# Sheet_2.net
KiCad netlist of a schematic drawn in EasyEDA
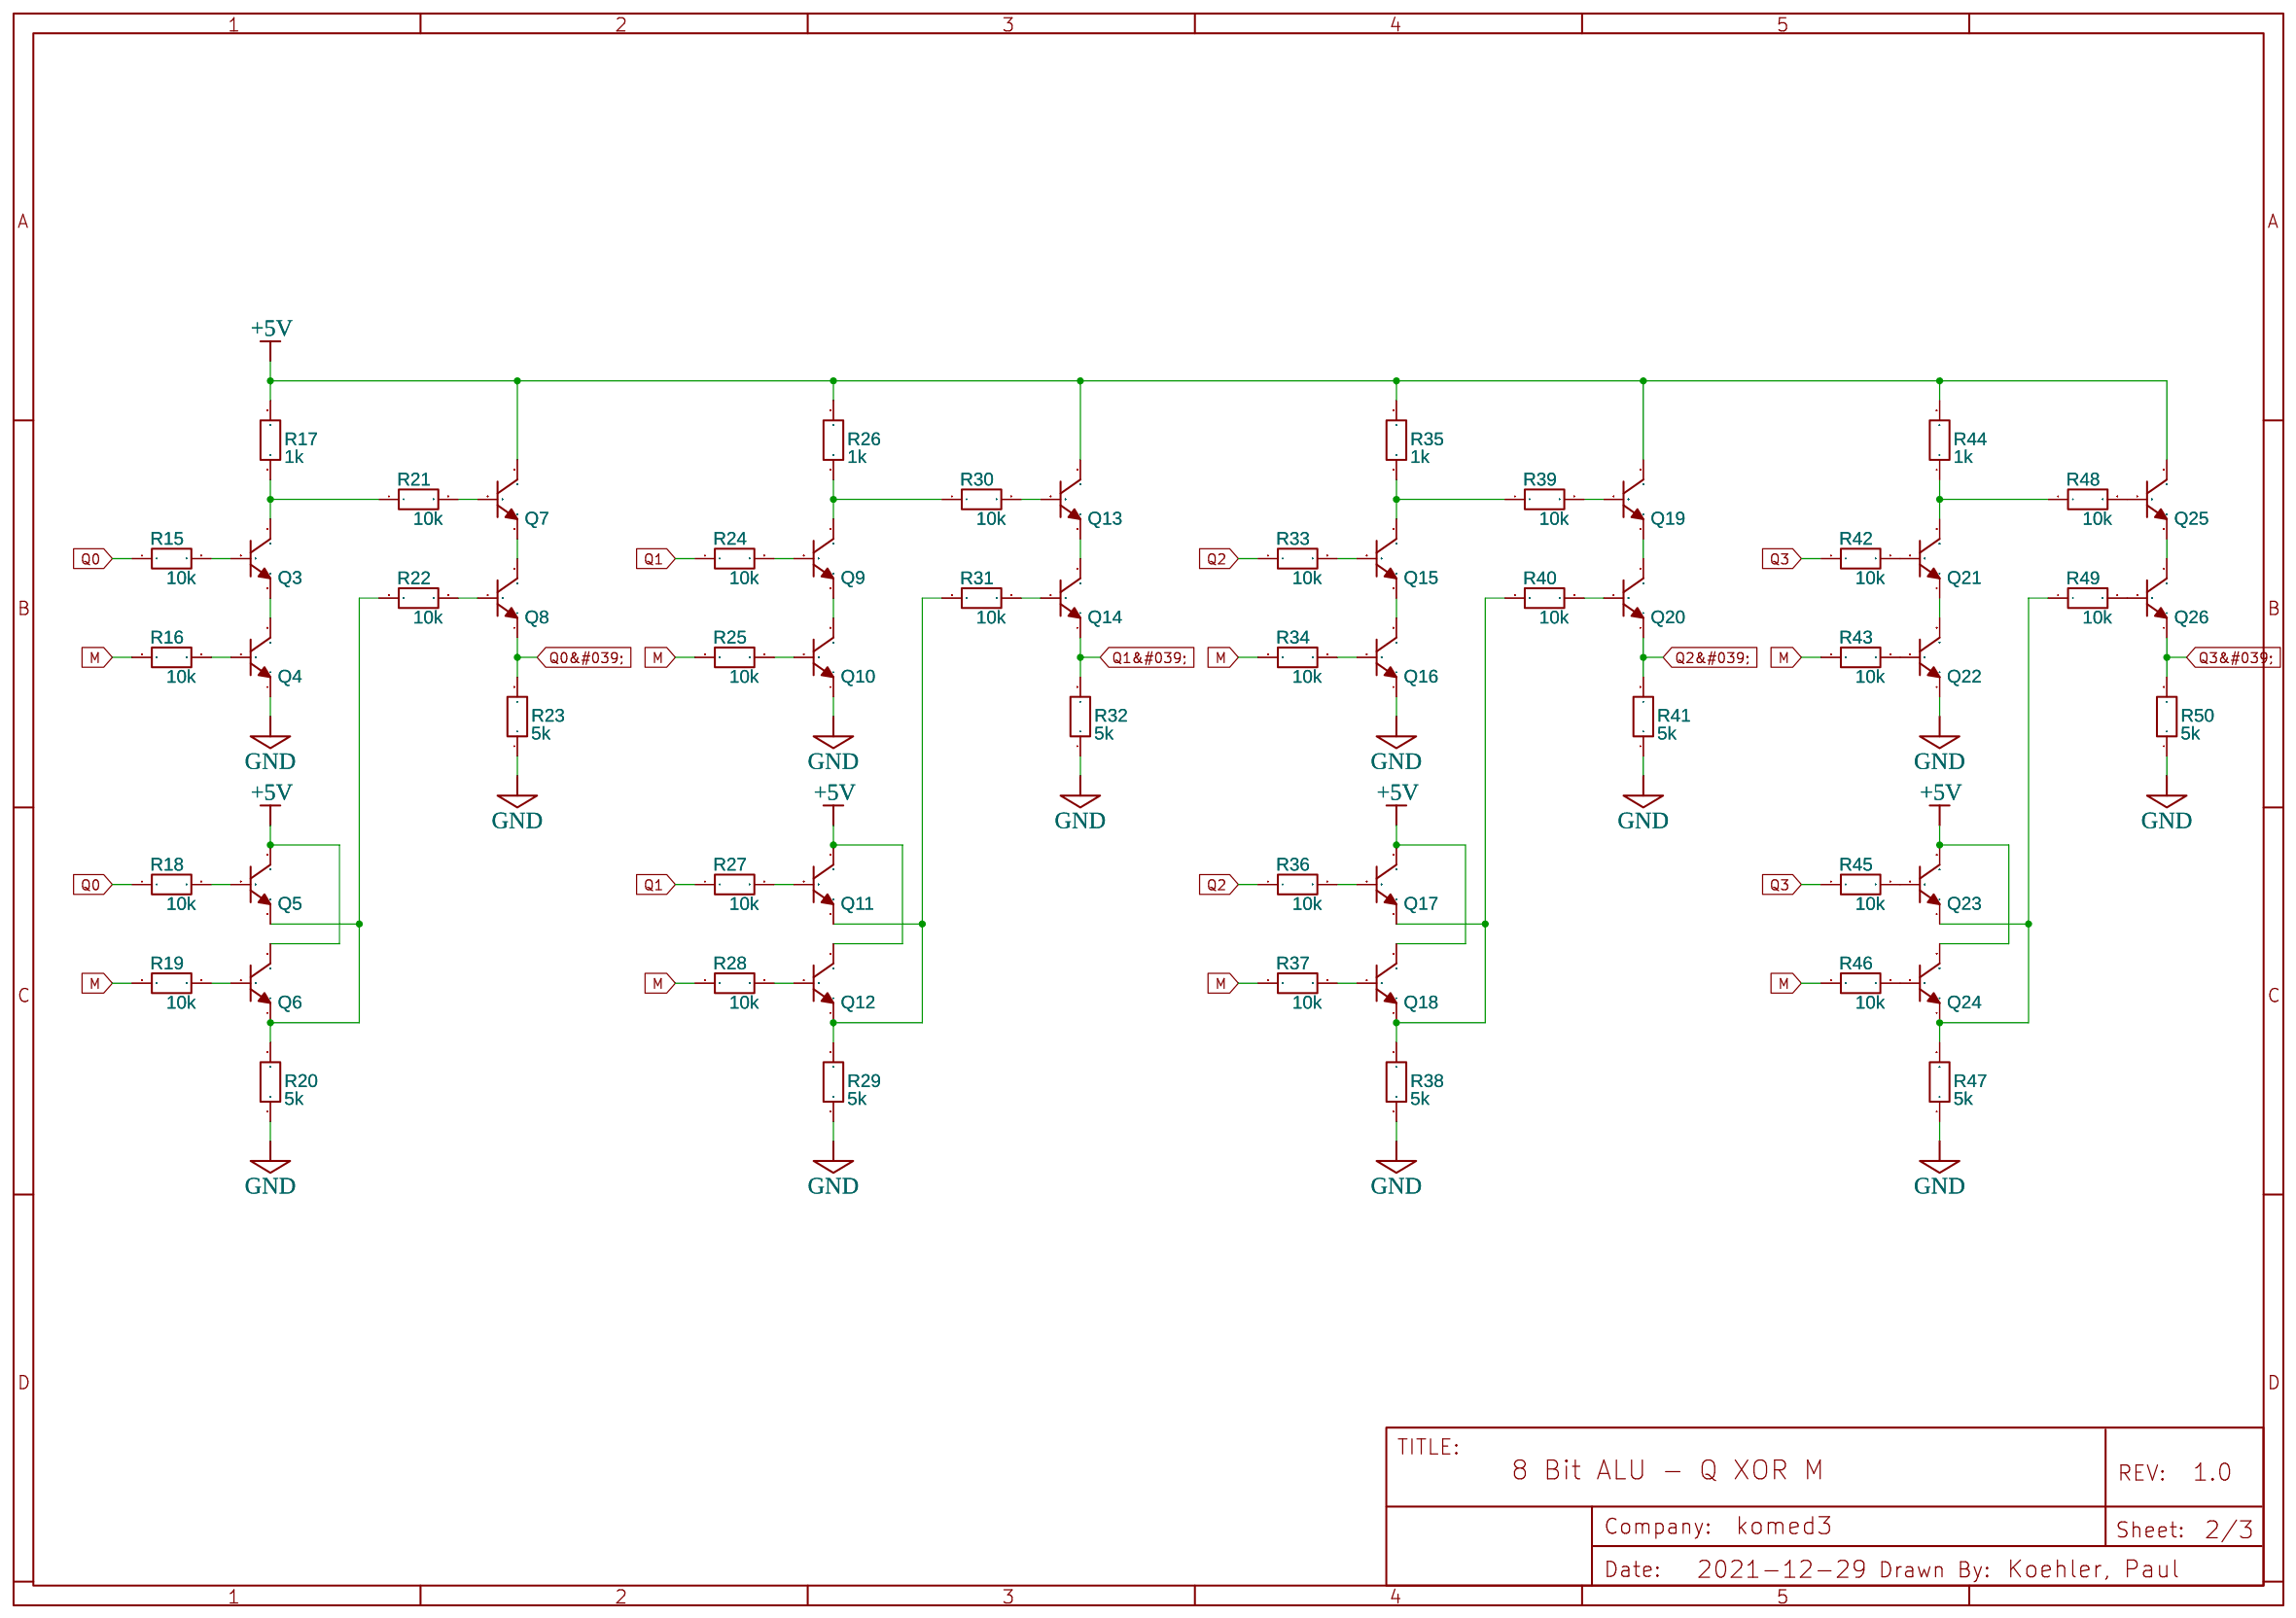
[diagram p0: schematic sheet]

(export (version "E")
  (design (tool "Eeschema 10.0.6"))
  (components
    (comp (ref "Q3")
      (value "2N3904(TO-92)")
      (fields (field (name "BOM_Manufacturer Part") "2N3904") (field (name "BOM_Supplier Part") "C118538"))
      (libsource (lib "") (part "2N3904(TO-92)"))
    )
    (comp (ref "Q4")
      (value "2N3904(TO-92)")
      (fields (field (name "BOM_Manufacturer Part") "2N3904") (field (name "BOM_Supplier Part") "C118538"))
      (libsource (lib "") (part "2N3904(TO-92)"))
    )
    (comp (ref "Q5")
      (value "2N3904(TO-92)")
      (fields (field (name "BOM_Manufacturer Part") "2N3904") (field (name "BOM_Supplier Part") "C118538"))
      (libsource (lib "") (part "2N3904(TO-92)"))
    )
    (comp (ref "Q6")
      (value "2N3904(TO-92)")
      (fields (field (name "BOM_Manufacturer Part") "2N3904") (field (name "BOM_Supplier Part") "C118538"))
      (libsource (lib "") (part "2N3904(TO-92)"))
    )
    (comp (ref "Q7")
      (value "2N3904(TO-92)")
      (fields (field (name "BOM_Manufacturer Part") "2N3904") (field (name "BOM_Supplier Part") "C118538"))
      (libsource (lib "") (part "2N3904(TO-92)"))
    )
    (comp (ref "Q8")
      (value "2N3904(TO-92)")
      (fields (field (name "BOM_Manufacturer Part") "2N3904") (field (name "BOM_Supplier Part") "C118538"))
      (libsource (lib "") (part "2N3904(TO-92)"))
    )
    (comp (ref "Q9")
      (value "2N3904(TO-92)")
      (fields (field (name "BOM_Manufacturer Part") "2N3904") (field (name "BOM_Supplier Part") "C118538"))
      (libsource (lib "") (part "2N3904(TO-92)"))
    )
    (comp (ref "Q10")
      (value "2N3904(TO-92)")
      (fields (field (name "BOM_Manufacturer Part") "2N3904") (field (name "BOM_Supplier Part") "C118538"))
      (libsource (lib "") (part "2N3904(TO-92)"))
    )
    (comp (ref "Q11")
      (value "2N3904(TO-92)")
      (fields (field (name "BOM_Manufacturer Part") "2N3904") (field (name "BOM_Supplier Part") "C118538"))
      (libsource (lib "") (part "2N3904(TO-92)"))
    )
    (comp (ref "Q12")
      (value "2N3904(TO-92)")
      (fields (field (name "BOM_Manufacturer Part") "2N3904") (field (name "BOM_Supplier Part") "C118538"))
      (libsource (lib "") (part "2N3904(TO-92)"))
    )
    (comp (ref "Q13")
      (value "2N3904(TO-92)")
      (fields (field (name "BOM_Manufacturer Part") "2N3904") (field (name "BOM_Supplier Part") "C118538"))
      (libsource (lib "") (part "2N3904(TO-92)"))
    )
    (comp (ref "Q14")
      (value "2N3904(TO-92)")
      (fields (field (name "BOM_Manufacturer Part") "2N3904") (field (name "BOM_Supplier Part") "C118538"))
      (libsource (lib "") (part "2N3904(TO-92)"))
    )
    (comp (ref "Q15")
      (value "2N3904(TO-92)")
      (fields (field (name "BOM_Manufacturer Part") "2N3904") (field (name "BOM_Supplier Part") "C118538"))
      (libsource (lib "") (part "2N3904(TO-92)"))
    )
    (comp (ref "Q16")
      (value "2N3904(TO-92)")
      (fields (field (name "BOM_Manufacturer Part") "2N3904") (field (name "BOM_Supplier Part") "C118538"))
      (libsource (lib "") (part "2N3904(TO-92)"))
    )
    (comp (ref "Q17")
      (value "2N3904(TO-92)")
      (fields (field (name "BOM_Manufacturer Part") "2N3904") (field (name "BOM_Supplier Part") "C118538"))
      (libsource (lib "") (part "2N3904(TO-92)"))
    )
    (comp (ref "Q18")
      (value "2N3904(TO-92)")
      (fields (field (name "BOM_Manufacturer Part") "2N3904") (field (name "BOM_Supplier Part") "C118538"))
      (libsource (lib "") (part "2N3904(TO-92)"))
    )
    (comp (ref "Q19")
      (value "2N3904(TO-92)")
      (fields (field (name "BOM_Manufacturer Part") "2N3904") (field (name "BOM_Supplier Part") "C118538"))
      (libsource (lib "") (part "2N3904(TO-92)"))
    )
    (comp (ref "Q20")
      (value "2N3904(TO-92)")
      (fields (field (name "BOM_Manufacturer Part") "2N3904") (field (name "BOM_Supplier Part") "C118538"))
      (libsource (lib "") (part "2N3904(TO-92)"))
    )
    (comp (ref "Q21")
      (value "2N3904(TO-92)")
      (fields (field (name "BOM_Manufacturer Part") "2N3904") (field (name "BOM_Supplier Part") "C118538"))
      (libsource (lib "") (part "2N3904(TO-92)"))
    )
    (comp (ref "Q22")
      (value "2N3904(TO-92)")
      (fields (field (name "BOM_Manufacturer Part") "2N3904") (field (name "BOM_Supplier Part") "C118538"))
      (libsource (lib "") (part "2N3904(TO-92)"))
    )
    (comp (ref "Q23")
      (value "2N3904(TO-92)")
      (fields (field (name "BOM_Manufacturer Part") "2N3904") (field (name "BOM_Supplier Part") "C118538"))
      (libsource (lib "") (part "2N3904(TO-92)"))
    )
    (comp (ref "Q24")
      (value "2N3904(TO-92)")
      (fields (field (name "BOM_Manufacturer Part") "2N3904") (field (name "BOM_Supplier Part") "C118538"))
      (libsource (lib "") (part "2N3904(TO-92)"))
    )
    (comp (ref "Q25")
      (value "2N3904(TO-92)")
      (fields (field (name "BOM_Manufacturer Part") "2N3904") (field (name "BOM_Supplier Part") "C118538"))
      (libsource (lib "") (part "2N3904(TO-92)"))
    )
    (comp (ref "Q26")
      (value "2N3904(TO-92)")
      (fields (field (name "BOM_Manufacturer Part") "2N3904") (field (name "BOM_Supplier Part") "C118538"))
      (libsource (lib "") (part "2N3904(TO-92)"))
    )
    (comp (ref "R15") (value "10k") (libsource (lib "") (part "R_AXIAL-0.3_EU")))
    (comp (ref "R16") (value "10k") (libsource (lib "") (part "R_AXIAL-0.3_EU")))
    (comp (ref "R17") (value "1k") (libsource (lib "") (part "R_AXIAL-0.3_EU_1")))
    (comp (ref "R18") (value "10k") (libsource (lib "") (part "R_AXIAL-0.3_EU")))
    (comp (ref "R19") (value "10k") (libsource (lib "") (part "R_AXIAL-0.3_EU")))
    (comp (ref "R20") (value "5k") (libsource (lib "") (part "R_AXIAL-0.3_EU_1")))
    (comp (ref "R21") (value "10k") (libsource (lib "") (part "R_AXIAL-0.3_EU")))
    (comp (ref "R22") (value "10k") (libsource (lib "") (part "R_AXIAL-0.3_EU")))
    (comp (ref "R23") (value "5k") (libsource (lib "") (part "R_AXIAL-0.3_EU_1")))
    (comp (ref "R24") (value "10k") (libsource (lib "") (part "R_AXIAL-0.3_EU")))
    (comp (ref "R25") (value "10k") (libsource (lib "") (part "R_AXIAL-0.3_EU")))
    (comp (ref "R26") (value "1k") (libsource (lib "") (part "R_AXIAL-0.3_EU_1")))
    (comp (ref "R27") (value "10k") (libsource (lib "") (part "R_AXIAL-0.3_EU")))
    (comp (ref "R28") (value "10k") (libsource (lib "") (part "R_AXIAL-0.3_EU")))
    (comp (ref "R29") (value "5k") (libsource (lib "") (part "R_AXIAL-0.3_EU_1")))
    (comp (ref "R30") (value "10k") (libsource (lib "") (part "R_AXIAL-0.3_EU")))
    (comp (ref "R31") (value "10k") (libsource (lib "") (part "R_AXIAL-0.3_EU")))
    (comp (ref "R32") (value "5k") (libsource (lib "") (part "R_AXIAL-0.3_EU_1")))
    (comp (ref "R33") (value "10k") (libsource (lib "") (part "R_AXIAL-0.3_EU")))
    (comp (ref "R34") (value "10k") (libsource (lib "") (part "R_AXIAL-0.3_EU")))
    (comp (ref "R35") (value "1k") (libsource (lib "") (part "R_AXIAL-0.3_EU_1")))
    (comp (ref "R36") (value "10k") (libsource (lib "") (part "R_AXIAL-0.3_EU")))
    (comp (ref "R37") (value "10k") (libsource (lib "") (part "R_AXIAL-0.3_EU")))
    (comp (ref "R38") (value "5k") (libsource (lib "") (part "R_AXIAL-0.3_EU_1")))
    (comp (ref "R39") (value "10k") (libsource (lib "") (part "R_AXIAL-0.3_EU")))
    (comp (ref "R40") (value "10k") (libsource (lib "") (part "R_AXIAL-0.3_EU")))
    (comp (ref "R41") (value "5k") (libsource (lib "") (part "R_AXIAL-0.3_EU_1")))
    (comp (ref "R42") (value "10k") (libsource (lib "") (part "R_AXIAL-0.3_EU")))
    (comp (ref "R43") (value "10k") (libsource (lib "") (part "R_AXIAL-0.3_EU")))
    (comp (ref "R44") (value "1k") (libsource (lib "") (part "R_AXIAL-0.3_EU_1")))
    (comp (ref "R45") (value "10k") (libsource (lib "") (part "R_AXIAL-0.3_EU")))
    (comp (ref "R46") (value "10k") (libsource (lib "") (part "R_AXIAL-0.3_EU")))
    (comp (ref "R47") (value "5k") (libsource (lib "") (part "R_AXIAL-0.3_EU_1")))
    (comp (ref "R48") (value "10k") (libsource (lib "") (part "R_AXIAL-0.3_EU")))
    (comp (ref "R49") (value "10k") (libsource (lib "") (part "R_AXIAL-0.3_EU")))
    (comp (ref "R50") (value "5k") (libsource (lib "") (part "R_AXIAL-0.3_EU_1")))
  )
  (nets
    (net (code "1") (name "+5V") (class "Default")
      (node (ref "Q11") (pin "3") (pinfunction "C_3") (pintype "unspecified"))
      (node (ref "Q12") (pin "3") (pinfunction "C_3") (pintype "unspecified"))
      (node (ref "Q13") (pin "3") (pinfunction "C_3") (pintype "unspecified"))
      (node (ref "Q17") (pin "3") (pinfunction "C_3") (pintype "unspecified"))
      (node (ref "Q18") (pin "3") (pinfunction "C_3") (pintype "unspecified"))
      (node (ref "Q19") (pin "3") (pinfunction "C_3") (pintype "unspecified"))
      (node (ref "Q23") (pin "3") (pinfunction "C_3") (pintype "unspecified"))
      (node (ref "Q24") (pin "3") (pinfunction "C_3") (pintype "unspecified"))
      (node (ref "Q25") (pin "3") (pinfunction "C_3") (pintype "unspecified"))
      (node (ref "Q5") (pin "3") (pinfunction "C_3") (pintype "unspecified"))
      (node (ref "Q6") (pin "3") (pinfunction "C_3") (pintype "unspecified"))
      (node (ref "Q7") (pin "3") (pinfunction "C_3") (pintype "unspecified"))
      (node (ref "R17") (pin "2") (pinfunction "2_2") (pintype "unspecified"))
      (node (ref "R26") (pin "2") (pinfunction "2_2") (pintype "unspecified"))
      (node (ref "R35") (pin "2") (pinfunction "2_2") (pintype "unspecified"))
      (node (ref "R44") (pin "2") (pinfunction "2_2") (pintype "unspecified"))
    )
    (net (code "2") (name "GND") (class "Default")
      (node (ref "Q10") (pin "1") (pinfunction "E_1") (pintype "unspecified"))
      (node (ref "Q16") (pin "1") (pinfunction "E_1") (pintype "unspecified"))
      (node (ref "Q22") (pin "1") (pinfunction "E_1") (pintype "unspecified"))
      (node (ref "Q4") (pin "1") (pinfunction "E_1") (pintype "unspecified"))
      (node (ref "R20") (pin "1") (pinfunction "1_1") (pintype "unspecified"))
      (node (ref "R23") (pin "1") (pinfunction "1_1") (pintype "unspecified"))
      (node (ref "R29") (pin "1") (pinfunction "1_1") (pintype "unspecified"))
      (node (ref "R32") (pin "1") (pinfunction "1_1") (pintype "unspecified"))
      (node (ref "R38") (pin "1") (pinfunction "1_1") (pintype "unspecified"))
      (node (ref "R41") (pin "1") (pinfunction "1_1") (pintype "unspecified"))
      (node (ref "R47") (pin "1") (pinfunction "1_1") (pintype "unspecified"))
      (node (ref "R50") (pin "1") (pinfunction "1_1") (pintype "unspecified"))
    )
    (net (code "3") (name "M") (class "Default")
      (node (ref "R16") (pin "1") (pinfunction "1_1") (pintype "unspecified"))
      (node (ref "R19") (pin "1") (pinfunction "1_1") (pintype "unspecified"))
      (node (ref "R25") (pin "1") (pinfunction "1_1") (pintype "unspecified"))
      (node (ref "R28") (pin "1") (pinfunction "1_1") (pintype "unspecified"))
      (node (ref "R34") (pin "1") (pinfunction "1_1") (pintype "unspecified"))
      (node (ref "R37") (pin "1") (pinfunction "1_1") (pintype "unspecified"))
      (node (ref "R43") (pin "1") (pinfunction "1_1") (pintype "unspecified"))
      (node (ref "R46") (pin "1") (pinfunction "1_1") (pintype "unspecified"))
    )
    (net (code "4") (name "Net-(Q3-B)") (class "Default")
      (node (ref "Q3") (pin "2") (pinfunction "B_2") (pintype "unspecified"))
      (node (ref "R15") (pin "2") (pinfunction "2_2") (pintype "unspecified"))
    )
    (net (code "5") (name "Net-(Q3-C)") (class "Default")
      (node (ref "Q3") (pin "3") (pinfunction "C_3") (pintype "unspecified"))
      (node (ref "R17") (pin "1") (pinfunction "1_1") (pintype "unspecified"))
      (node (ref "R21") (pin "1") (pinfunction "1_1") (pintype "unspecified"))
    )
    (net (code "6") (name "Net-(Q3-E)") (class "Default")
      (node (ref "Q3") (pin "1") (pinfunction "E_1") (pintype "unspecified"))
      (node (ref "Q4") (pin "3") (pinfunction "C_3") (pintype "unspecified"))
    )
    (net (code "7") (name "Net-(Q4-B)") (class "Default")
      (node (ref "Q4") (pin "2") (pinfunction "B_2") (pintype "unspecified"))
      (node (ref "R16") (pin "2") (pinfunction "2_2") (pintype "unspecified"))
    )
    (net (code "8") (name "Net-(Q5-B)") (class "Default")
      (node (ref "Q5") (pin "2") (pinfunction "B_2") (pintype "unspecified"))
      (node (ref "R18") (pin "2") (pinfunction "2_2") (pintype "unspecified"))
    )
    (net (code "9") (name "Net-(Q5-E)") (class "Default")
      (node (ref "Q5") (pin "1") (pinfunction "E_1") (pintype "unspecified"))
      (node (ref "Q6") (pin "1") (pinfunction "E_1") (pintype "unspecified"))
      (node (ref "R20") (pin "2") (pinfunction "2_2") (pintype "unspecified"))
      (node (ref "R22") (pin "1") (pinfunction "1_1") (pintype "unspecified"))
    )
    (net (code "10") (name "Net-(Q6-B)") (class "Default")
      (node (ref "Q6") (pin "2") (pinfunction "B_2") (pintype "unspecified"))
      (node (ref "R19") (pin "2") (pinfunction "2_2") (pintype "unspecified"))
    )
    (net (code "11") (name "Net-(Q7-B)") (class "Default")
      (node (ref "Q7") (pin "2") (pinfunction "B_2") (pintype "unspecified"))
      (node (ref "R21") (pin "2") (pinfunction "2_2") (pintype "unspecified"))
    )
    (net (code "12") (name "Net-(Q7-E)") (class "Default")
      (node (ref "Q7") (pin "1") (pinfunction "E_1") (pintype "unspecified"))
      (node (ref "Q8") (pin "3") (pinfunction "C_3") (pintype "unspecified"))
    )
    (net (code "13") (name "Net-(Q8-B)") (class "Default")
      (node (ref "Q8") (pin "2") (pinfunction "B_2") (pintype "unspecified"))
      (node (ref "R22") (pin "2") (pinfunction "2_2") (pintype "unspecified"))
    )
    (net (code "14") (name "Net-(Q9-B)") (class "Default")
      (node (ref "Q9") (pin "2") (pinfunction "B_2") (pintype "unspecified"))
      (node (ref "R24") (pin "2") (pinfunction "2_2") (pintype "unspecified"))
    )
    (net (code "15") (name "Net-(Q9-C)") (class "Default")
      (node (ref "Q9") (pin "3") (pinfunction "C_3") (pintype "unspecified"))
      (node (ref "R26") (pin "1") (pinfunction "1_1") (pintype "unspecified"))
      (node (ref "R30") (pin "1") (pinfunction "1_1") (pintype "unspecified"))
    )
    (net (code "16") (name "Net-(Q10-B)") (class "Default")
      (node (ref "Q10") (pin "2") (pinfunction "B_2") (pintype "unspecified"))
      (node (ref "R25") (pin "2") (pinfunction "2_2") (pintype "unspecified"))
    )
    (net (code "17") (name "Net-(Q10-C)") (class "Default")
      (node (ref "Q10") (pin "3") (pinfunction "C_3") (pintype "unspecified"))
      (node (ref "Q9") (pin "1") (pinfunction "E_1") (pintype "unspecified"))
    )
    (net (code "18") (name "Net-(Q11-B)") (class "Default")
      (node (ref "Q11") (pin "2") (pinfunction "B_2") (pintype "unspecified"))
      (node (ref "R27") (pin "2") (pinfunction "2_2") (pintype "unspecified"))
    )
    (net (code "19") (name "Net-(Q11-E)") (class "Default")
      (node (ref "Q11") (pin "1") (pinfunction "E_1") (pintype "unspecified"))
      (node (ref "Q12") (pin "1") (pinfunction "E_1") (pintype "unspecified"))
      (node (ref "R29") (pin "2") (pinfunction "2_2") (pintype "unspecified"))
      (node (ref "R31") (pin "1") (pinfunction "1_1") (pintype "unspecified"))
    )
    (net (code "20") (name "Net-(Q12-B)") (class "Default")
      (node (ref "Q12") (pin "2") (pinfunction "B_2") (pintype "unspecified"))
      (node (ref "R28") (pin "2") (pinfunction "2_2") (pintype "unspecified"))
    )
    (net (code "21") (name "Net-(Q13-B)") (class "Default")
      (node (ref "Q13") (pin "2") (pinfunction "B_2") (pintype "unspecified"))
      (node (ref "R30") (pin "2") (pinfunction "2_2") (pintype "unspecified"))
    )
    (net (code "22") (name "Net-(Q13-E)") (class "Default")
      (node (ref "Q13") (pin "1") (pinfunction "E_1") (pintype "unspecified"))
      (node (ref "Q14") (pin "3") (pinfunction "C_3") (pintype "unspecified"))
    )
    (net (code "23") (name "Net-(Q14-B)") (class "Default")
      (node (ref "Q14") (pin "2") (pinfunction "B_2") (pintype "unspecified"))
      (node (ref "R31") (pin "2") (pinfunction "2_2") (pintype "unspecified"))
    )
    (net (code "24") (name "Net-(Q15-B)") (class "Default")
      (node (ref "Q15") (pin "2") (pinfunction "B_2") (pintype "unspecified"))
      (node (ref "R33") (pin "2") (pinfunction "2_2") (pintype "unspecified"))
    )
    (net (code "25") (name "Net-(Q15-C)") (class "Default")
      (node (ref "Q15") (pin "3") (pinfunction "C_3") (pintype "unspecified"))
      (node (ref "R35") (pin "1") (pinfunction "1_1") (pintype "unspecified"))
      (node (ref "R39") (pin "1") (pinfunction "1_1") (pintype "unspecified"))
    )
    (net (code "26") (name "Net-(Q15-E)") (class "Default")
      (node (ref "Q15") (pin "1") (pinfunction "E_1") (pintype "unspecified"))
      (node (ref "Q16") (pin "3") (pinfunction "C_3") (pintype "unspecified"))
    )
    (net (code "27") (name "Net-(Q16-B)") (class "Default")
      (node (ref "Q16") (pin "2") (pinfunction "B_2") (pintype "unspecified"))
      (node (ref "R34") (pin "2") (pinfunction "2_2") (pintype "unspecified"))
    )
    (net (code "28") (name "Net-(Q17-B)") (class "Default")
      (node (ref "Q17") (pin "2") (pinfunction "B_2") (pintype "unspecified"))
      (node (ref "R36") (pin "2") (pinfunction "2_2") (pintype "unspecified"))
    )
    (net (code "29") (name "Net-(Q17-E)") (class "Default")
      (node (ref "Q17") (pin "1") (pinfunction "E_1") (pintype "unspecified"))
      (node (ref "Q18") (pin "1") (pinfunction "E_1") (pintype "unspecified"))
      (node (ref "R38") (pin "2") (pinfunction "2_2") (pintype "unspecified"))
      (node (ref "R40") (pin "1") (pinfunction "1_1") (pintype "unspecified"))
    )
    (net (code "30") (name "Net-(Q18-B)") (class "Default")
      (node (ref "Q18") (pin "2") (pinfunction "B_2") (pintype "unspecified"))
      (node (ref "R37") (pin "2") (pinfunction "2_2") (pintype "unspecified"))
    )
    (net (code "31") (name "Net-(Q19-B)") (class "Default")
      (node (ref "Q19") (pin "2") (pinfunction "B_2") (pintype "unspecified"))
      (node (ref "R39") (pin "2") (pinfunction "2_2") (pintype "unspecified"))
    )
    (net (code "32") (name "Net-(Q19-E)") (class "Default")
      (node (ref "Q19") (pin "1") (pinfunction "E_1") (pintype "unspecified"))
      (node (ref "Q20") (pin "3") (pinfunction "C_3") (pintype "unspecified"))
    )
    (net (code "33") (name "Net-(Q20-B)") (class "Default")
      (node (ref "Q20") (pin "2") (pinfunction "B_2") (pintype "unspecified"))
      (node (ref "R40") (pin "2") (pinfunction "2_2") (pintype "unspecified"))
    )
    (net (code "34") (name "Net-(Q21-B)") (class "Default")
      (node (ref "Q21") (pin "2") (pinfunction "B_2") (pintype "unspecified"))
      (node (ref "R42") (pin "2") (pinfunction "2_2") (pintype "unspecified"))
    )
    (net (code "35") (name "Net-(Q21-C)") (class "Default")
      (node (ref "Q21") (pin "3") (pinfunction "C_3") (pintype "unspecified"))
      (node (ref "R44") (pin "1") (pinfunction "1_1") (pintype "unspecified"))
      (node (ref "R48") (pin "1") (pinfunction "1_1") (pintype "unspecified"))
    )
    (net (code "36") (name "Net-(Q21-E)") (class "Default")
      (node (ref "Q21") (pin "1") (pinfunction "E_1") (pintype "unspecified"))
      (node (ref "Q22") (pin "3") (pinfunction "C_3") (pintype "unspecified"))
    )
    (net (code "37") (name "Net-(Q22-B)") (class "Default")
      (node (ref "Q22") (pin "2") (pinfunction "B_2") (pintype "unspecified"))
      (node (ref "R43") (pin "2") (pinfunction "2_2") (pintype "unspecified"))
    )
    (net (code "38") (name "Net-(Q23-B)") (class "Default")
      (node (ref "Q23") (pin "2") (pinfunction "B_2") (pintype "unspecified"))
      (node (ref "R45") (pin "2") (pinfunction "2_2") (pintype "unspecified"))
    )
    (net (code "39") (name "Net-(Q23-E)") (class "Default")
      (node (ref "Q23") (pin "1") (pinfunction "E_1") (pintype "unspecified"))
      (node (ref "Q24") (pin "1") (pinfunction "E_1") (pintype "unspecified"))
      (node (ref "R47") (pin "2") (pinfunction "2_2") (pintype "unspecified"))
      (node (ref "R49") (pin "1") (pinfunction "1_1") (pintype "unspecified"))
    )
    (net (code "40") (name "Net-(Q24-B)") (class "Default")
      (node (ref "Q24") (pin "2") (pinfunction "B_2") (pintype "unspecified"))
      (node (ref "R46") (pin "2") (pinfunction "2_2") (pintype "unspecified"))
    )
    (net (code "41") (name "Net-(Q25-B)") (class "Default")
      (node (ref "Q25") (pin "2") (pinfunction "B_2") (pintype "unspecified"))
      (node (ref "R48") (pin "2") (pinfunction "2_2") (pintype "unspecified"))
    )
    (net (code "42") (name "Net-(Q25-E)") (class "Default")
      (node (ref "Q25") (pin "1") (pinfunction "E_1") (pintype "unspecified"))
      (node (ref "Q26") (pin "3") (pinfunction "C_3") (pintype "unspecified"))
    )
    (net (code "43") (name "Net-(Q26-B)") (class "Default")
      (node (ref "Q26") (pin "2") (pinfunction "B_2") (pintype "unspecified"))
      (node (ref "R49") (pin "2") (pinfunction "2_2") (pintype "unspecified"))
    )
    (net (code "44") (name "Q0") (class "Default")
      (node (ref "R15") (pin "1") (pinfunction "1_1") (pintype "unspecified"))
      (node (ref "R18") (pin "1") (pinfunction "1_1") (pintype "unspecified"))
    )
    (net (code "45") (name "Q0&#039;") (class "Default")
      (node (ref "Q8") (pin "1") (pinfunction "E_1") (pintype "unspecified"))
      (node (ref "R23") (pin "2") (pinfunction "2_2") (pintype "unspecified"))
    )
    (net (code "46") (name "Q1") (class "Default")
      (node (ref "R24") (pin "1") (pinfunction "1_1") (pintype "unspecified"))
      (node (ref "R27") (pin "1") (pinfunction "1_1") (pintype "unspecified"))
    )
    (net (code "47") (name "Q1&#039;") (class "Default")
      (node (ref "Q14") (pin "1") (pinfunction "E_1") (pintype "unspecified"))
      (node (ref "R32") (pin "2") (pinfunction "2_2") (pintype "unspecified"))
    )
    (net (code "48") (name "Q2") (class "Default")
      (node (ref "R33") (pin "1") (pinfunction "1_1") (pintype "unspecified"))
      (node (ref "R36") (pin "1") (pinfunction "1_1") (pintype "unspecified"))
    )
    (net (code "49") (name "Q2&#039;") (class "Default")
      (node (ref "Q20") (pin "1") (pinfunction "E_1") (pintype "unspecified"))
      (node (ref "R41") (pin "2") (pinfunction "2_2") (pintype "unspecified"))
    )
    (net (code "50") (name "Q3") (class "Default")
      (node (ref "R42") (pin "1") (pinfunction "1_1") (pintype "unspecified"))
      (node (ref "R45") (pin "1") (pinfunction "1_1") (pintype "unspecified"))
    )
    (net (code "51") (name "Q3&#039;") (class "Default")
      (node (ref "Q26") (pin "1") (pinfunction "E_1") (pintype "unspecified"))
      (node (ref "R50") (pin "2") (pinfunction "2_2") (pintype "unspecified"))
    )
  )
)
